# PROTECTION_SupplySwitching.net
KiCad netlist of a schematic drawn in Altium Designer
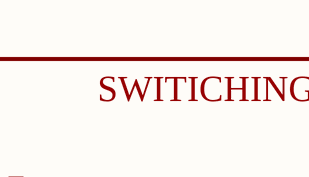
[diagram p0: PROTECTION&SupplySwitching.SchDoc, top left]
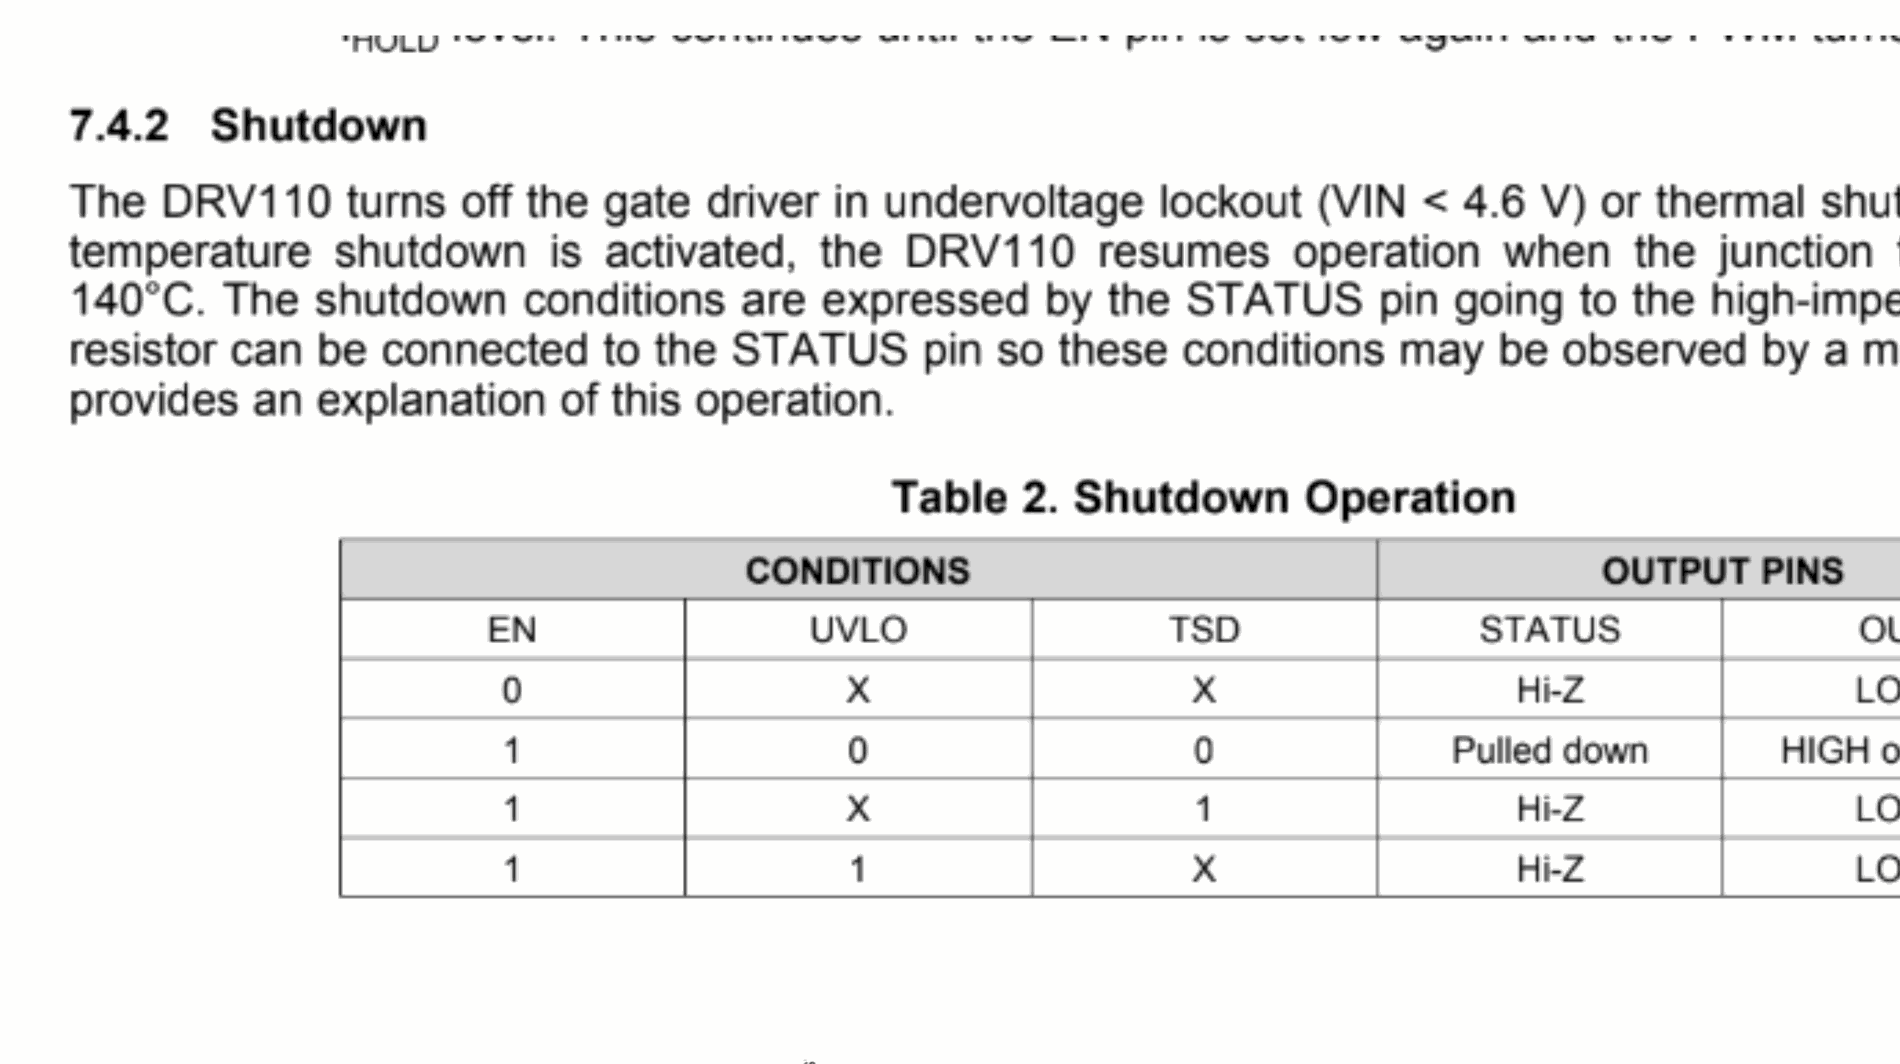
[diagram p1: PROTECTION&SupplySwitching.SchDoc, top middle]
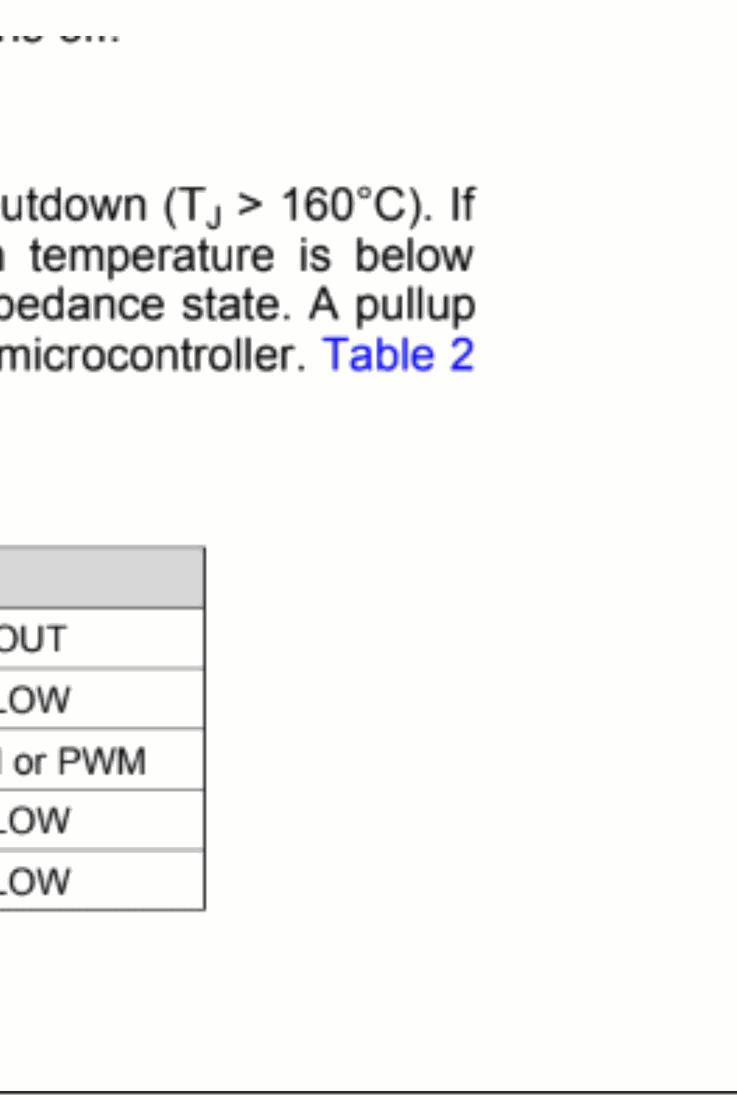
[diagram p2: PROTECTION&SupplySwitching.SchDoc, top right]
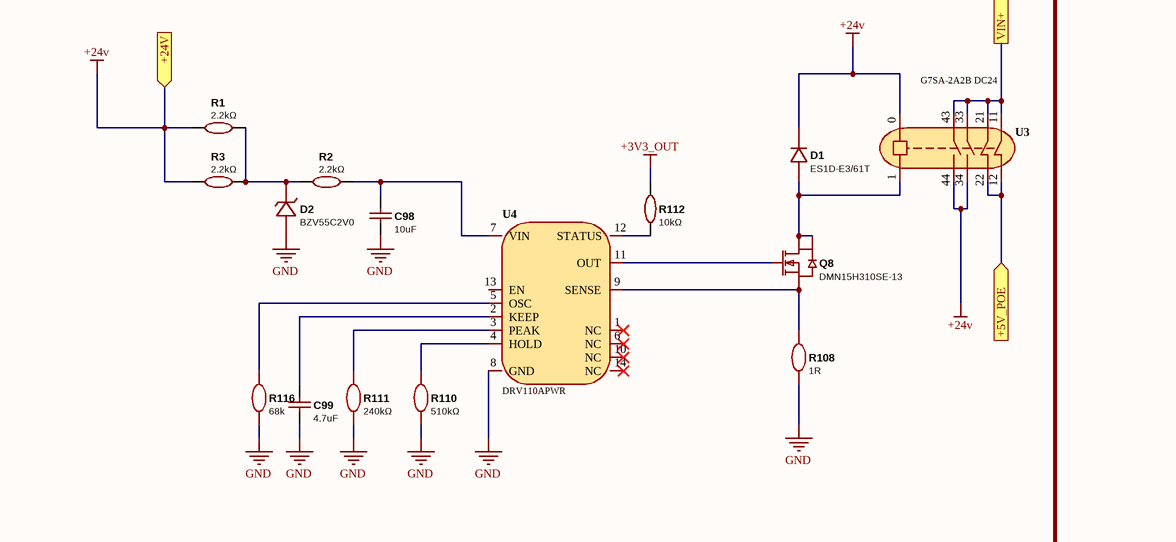
[diagram p3: PROTECTION&SupplySwitching.SchDoc, bottom left]
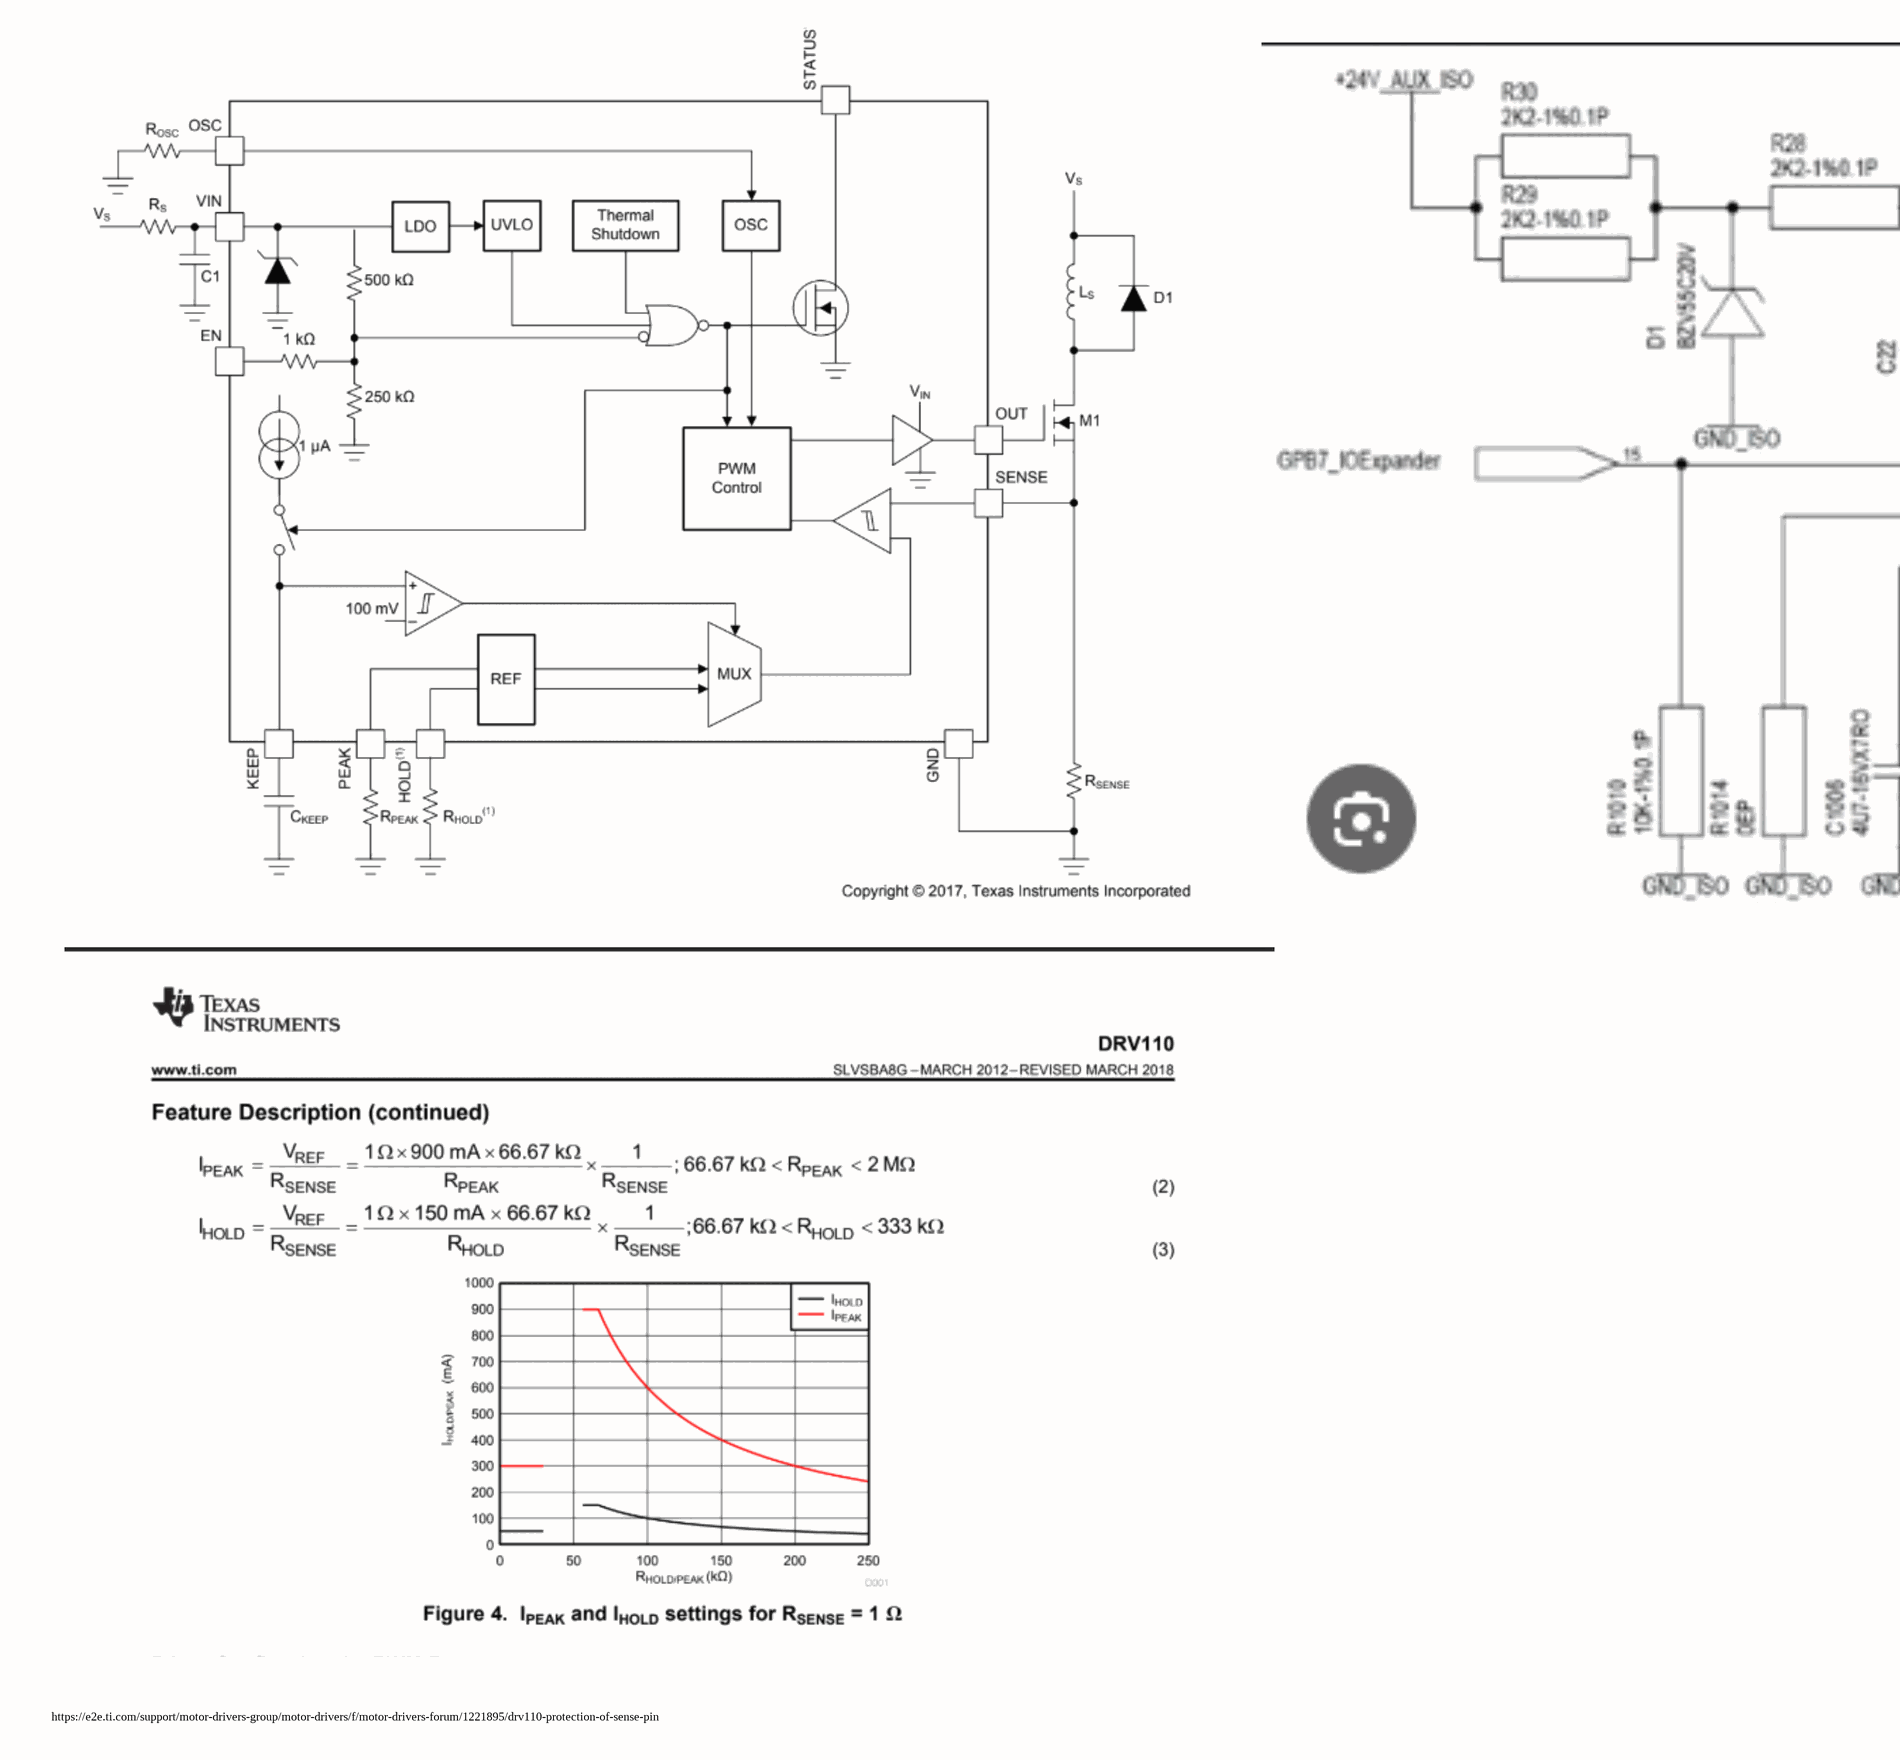
[diagram p4: PROTECTION&SupplySwitching.SchDoc, bottom middle]
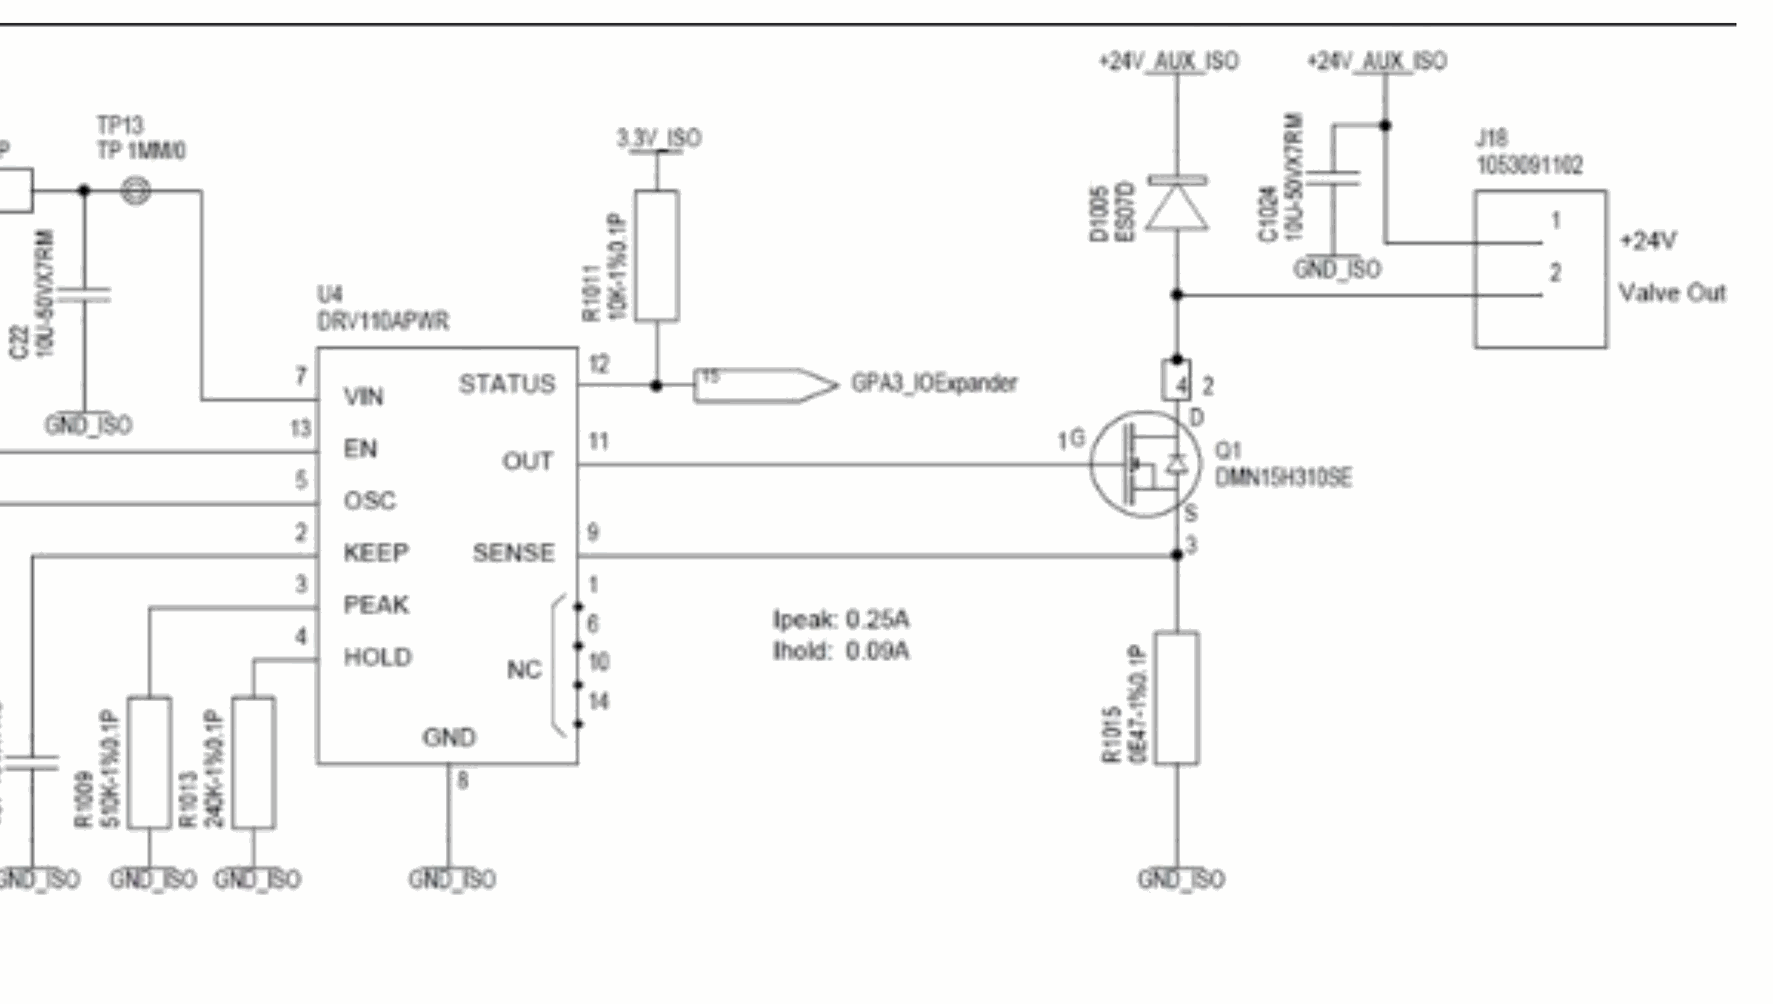
[diagram p5: PROTECTION&SupplySwitching.SchDoc, bottom right]

(export (version "E")
  (design (tool "Eeschema 10.0.6"))
  (components
    (comp (ref "C98")
      (value "10uF")
      (footprint "C_1206")
      (fields
        (field (name "MANUFACTURER PART") "CL31A106KBHNNNE")
        (field (name "MANUFACTURER") "SAMSUNG(三星)")
      )
      (libsource (lib "altium-import") (part "root_1_10uF_"))
    )
    (comp (ref "C99")
      (value "4.7uF")
      (footprint "C_1206")
      (fields
        (field (name "MANUFACTURER PART") "CL31B475KBHNNNE")
        (field (name "MANUFACTURER") "SAMSUNG(三星)")
      )
      (libsource (lib "altium-import") (part "root_1_4.7uF_"))
    )
    (comp (ref "D1")
      (value "ES1D-E3/61T")
      (footprint "SMA_L4.3-W2.6-LS5.2-RD")
      (fields (field (name "MANUFACTURER") "VISHAY(威世)"))
      (libsource (lib "altium-import") (part "root_3_ES1D-E3/61T_"))
    )
    (comp (ref "D2")
      (value "BZV55C2V0")
      (footprint "SOD-80_L3.5-W1.5-RD")
      (fields (field (name "MANUFACTURER") "LGE(鲁光)") (field (name "CONTRIBUTOR") "LCSC"))
      (libsource (lib "altium-import") (part "root_3_BZV55C2V0_"))
    )
    (comp (ref "Q8")
      (value "DMN15H310SE-13")
      (footprint "SOT-223-3_L6.5-W3.4-P2.30-LS7.0-BR")
      (fields (field (name "MANUFACTURER") "DIODES(美台)") (field (name "CONTRIBUTOR") "LCSC"))
      (libsource (lib "altium-import") (part "root_0_DMN15H310SE-13_"))
    )
    (comp (ref "R1")
      (value "2.2kΩ")
      (footprint "R_0805")
      (fields (field (name "MANUFACTURER") "YAGEO(国巨)") (field (name "MANUFACTURER PART") "RC0805FR-072K2L"))
      (libsource (lib "altium-import") (part "root_0_2.2kΩ_"))
    )
    (comp (ref "R2")
      (value "2.2kΩ")
      (footprint "R_0805")
      (fields (field (name "MANUFACTURER") "YAGEO(国巨)") (field (name "MANUFACTURER PART") "RC0805FR-072K2L"))
      (libsource (lib "altium-import") (part "root_0_2.2kΩ_"))
    )
    (comp (ref "R3")
      (value "2.2kΩ")
      (footprint "R_0805")
      (fields (field (name "MANUFACTURER") "YAGEO(国巨)") (field (name "MANUFACTURER PART") "RC0805FR-072K2L"))
      (libsource (lib "altium-import") (part "root_0_2.2kΩ_"))
    )
    (comp (ref "R108")
      (value "1R")
      (footprint "R_1206")
      (fields
        (field (name "MANUFACTURER PART") "RC1206FR-071RL")
        (field (name "MANUFACTURER") "YAGEO")
        (field (name "CONTRIBUTOR") "LCEDA_Lib")
      )
      (libsource (lib "altium-import") (part "root_1_0.47R_"))
    )
    (comp (ref "R110")
      (value "510kΩ")
      (footprint "R_0805")
      (fields
        (field (name "MANUFACTURER") "YAGEO(国巨)")
        (field (name "MANUFACTURER PART") "RT0805BRB07510KL")
        (field (name "CONTRIBUTOR") "lcsc")
      )
      (libsource (lib "altium-import") (part "root_1_510kΩ_"))
    )
    (comp (ref "R111")
      (value "240kΩ")
      (footprint "R_0805")
      (fields
        (field (name "MANUFACTURER") "YAGEO(国巨)")
        (field (name "MANUFACTURER PART") "RT0805BRD07240KL")
        (field (name "CONTRIBUTOR") "lcsc")
      )
      (libsource (lib "altium-import") (part "root_1_240kΩ_"))
    )
    (comp (ref "R112")
      (value "10kΩ")
      (footprint "R_0805")
      (fields (field (name "MANUFACTURER") "YAGEO(国巨)") (field (name "MANUFACTURER PART") "RT0805BRD0710KL"))
      (libsource (lib "altium-import") (part "root_1_10kΩ_"))
    )
    (comp (ref "R116")
      (value "68k")
      (footprint "R_0805")
      (fields
        (field (name "MANUFACTURER") "YAGEO")
        (field (name "MANUFACTURER PART") "RC0805FR-0768KL")
        (field (name "CONTRIBUTOR") "lcsc")
      )
      (libsource (lib "altium-import") (part "root_1_240kΩ_"))
    )
    (comp (ref "U3")
      (value "G7SA-2A2B DC24")
      (footprint "RELAY-TH_G7SA-2A2B")
      (fields (field (name "MANUFACTURER") "OMRON(欧姆龙)"))
      (libsource (lib "EsoCore_Edge_Board_V1-0.0.0") (part "G7SA-2A2B DC24"))
    )
    (comp (ref "U4")
      (value "DRV110APWR")
      (footprint "TSSOP-14_L5.0-W4.4-P0.65-LS6.4-BL")
      (fields (field (name "MANUFACTURER") "TI(德州仪器)"))
      (libsource (lib "EsoCore_Edge_Board_V1-0.0.0") (part "DRV110APWR"))
    )
  )
  (nets
    (net (code "1") (name "+3V3_OUT") (class "Default")
      (node (ref "R112") (pin "2") (pinfunction "2_2") (pintype "passive"))
    )
    (net (code "2") (name "+24v") (class "Default")
      (node (ref "D1") (pin "1") (pinfunction "C_1") (pintype "passive"))
      (node (ref "R1") (pin "1") (pinfunction "1_1") (pintype "passive"))
      (node (ref "R3") (pin "1") (pinfunction "1_1") (pintype "passive"))
      (node (ref "U3") (pin "0") (pinfunction "0_0") (pintype "passive"))
      (node (ref "U3") (pin "34") (pinfunction "34_34") (pintype "passive"))
      (node (ref "U3") (pin "44") (pinfunction "44_44") (pintype "passive"))
    )
    (net (code "3") (name "/+5V_POE") (class "Default")
      (node (ref "U3") (pin "12") (pinfunction "12_12") (pintype "passive"))
      (node (ref "U3") (pin "22") (pinfunction "22_22") (pintype "passive"))
    )
    (net (code "4") (name "/VIN+") (class "Default")
      (node (ref "U3") (pin "11") (pinfunction "11_11") (pintype "passive"))
      (node (ref "U3") (pin "21") (pinfunction "21_21") (pintype "passive"))
      (node (ref "U3") (pin "33") (pinfunction "33_33") (pintype "passive"))
      (node (ref "U3") (pin "43") (pinfunction "43_43") (pintype "passive"))
    )
    (net (code "5") (name "GND") (class "Default")
      (node (ref "C98") (pin "1") (pinfunction "1_1") (pintype "passive"))
      (node (ref "C99") (pin "1") (pinfunction "1_1") (pintype "passive"))
      (node (ref "D2") (pin "2") (pinfunction "A_2") (pintype "passive"))
      (node (ref "R108") (pin "1") (pinfunction "1_1") (pintype "passive"))
      (node (ref "R110") (pin "1") (pinfunction "1_1") (pintype "passive"))
      (node (ref "R111") (pin "1") (pinfunction "1_1") (pintype "passive"))
      (node (ref "R116") (pin "1") (pinfunction "1_1") (pintype "passive"))
      (node (ref "U4") (pin "8") (pinfunction "GND_8") (pintype "passive"))
    )
    (net (code "6") (name "Net-(D1-A)") (class "Default")
      (node (ref "D1") (pin "2") (pinfunction "A_2") (pintype "passive"))
      (node (ref "Q8") (pin "2") (pinfunction "D_2") (pintype "passive"))
      (node (ref "Q8") (pin "4") (pinfunction "D_4") (pintype "passive"))
      (node (ref "U3") (pin "1") (pinfunction "1_1") (pintype "passive"))
    )
    (net (code "7") (name "Net-(D2-K)") (class "Default")
      (node (ref "D2") (pin "1") (pinfunction "K_1") (pintype "passive"))
      (node (ref "R1") (pin "2") (pinfunction "2_2") (pintype "passive"))
      (node (ref "R2") (pin "1") (pinfunction "1_1") (pintype "passive"))
      (node (ref "R3") (pin "2") (pinfunction "2_2") (pintype "passive"))
    )
    (net (code "8") (name "Net-(Q8-G)") (class "Default")
      (node (ref "Q8") (pin "1") (pinfunction "G_1") (pintype "passive"))
      (node (ref "U4") (pin "11") (pinfunction "OUT_11") (pintype "passive"))
    )
    (net (code "9") (name "Net-(Q8-S)") (class "Default")
      (node (ref "Q8") (pin "3") (pinfunction "S_3") (pintype "passive"))
      (node (ref "R108") (pin "2") (pinfunction "2_2") (pintype "passive"))
      (node (ref "U4") (pin "9") (pinfunction "SENSE_9") (pintype "passive"))
    )
    (net (code "10") (name "Net-(U4-HOLD)") (class "Default")
      (node (ref "R110") (pin "2") (pinfunction "2_2") (pintype "passive"))
      (node (ref "U4") (pin "4") (pinfunction "HOLD_4") (pintype "passive"))
    )
    (net (code "11") (name "Net-(U4-KEEP)") (class "Default")
      (node (ref "C99") (pin "2") (pinfunction "2_2") (pintype "passive"))
      (node (ref "U4") (pin "2") (pinfunction "KEEP_2") (pintype "passive"))
    )
    (net (code "12") (name "Net-(U4-OSC)") (class "Default")
      (node (ref "R116") (pin "2") (pinfunction "2_2") (pintype "passive"))
      (node (ref "U4") (pin "5") (pinfunction "OSC_5") (pintype "passive"))
    )
    (net (code "13") (name "Net-(U4-PEAK)") (class "Default")
      (node (ref "R111") (pin "2") (pinfunction "2_2") (pintype "passive"))
      (node (ref "U4") (pin "3") (pinfunction "PEAK_3") (pintype "passive"))
    )
    (net (code "14") (name "Net-(U4-STATUS)") (class "Default")
      (node (ref "R112") (pin "1") (pinfunction "1_1") (pintype "passive"))
      (node (ref "U4") (pin "12") (pinfunction "STATUS_12") (pintype "passive"))
    )
    (net (code "15") (name "Net-(U4-VIN)") (class "Default")
      (node (ref "C98") (pin "2") (pinfunction "2_2") (pintype "passive"))
      (node (ref "R2") (pin "2") (pinfunction "2_2") (pintype "passive"))
      (node (ref "U4") (pin "7") (pinfunction "VIN_7") (pintype "passive"))
    )
    (net (code "16") (name "unconnected-(U4-EN-Pad13)") (class "Default")
      (node (ref "U4") (pin "13") (pinfunction "EN_13") (pintype "passive"))
    )
    (net (code "17") (name "unconnected-(U4-NC-Pad1)") (class "Default")
      (node (ref "U4") (pin "1") (pinfunction "NC_1") (pintype "passive+no_connect"))
    )
    (net (code "18") (name "unconnected-(U4-NC-Pad6)") (class "Default")
      (node (ref "U4") (pin "6") (pinfunction "NC_6") (pintype "passive+no_connect"))
    )
    (net (code "19") (name "unconnected-(U4-NC-Pad10)") (class "Default")
      (node (ref "U4") (pin "10") (pinfunction "NC_10") (pintype "passive+no_connect"))
    )
    (net (code "20") (name "unconnected-(U4-NC-Pad14)") (class "Default")
      (node (ref "U4") (pin "14") (pinfunction "NC_14") (pintype "passive+no_connect"))
    )
  )
)
